# USB2Serial_FT232RL_v1_0.net
KiCad netlist of a schematic drawn in EAGLE
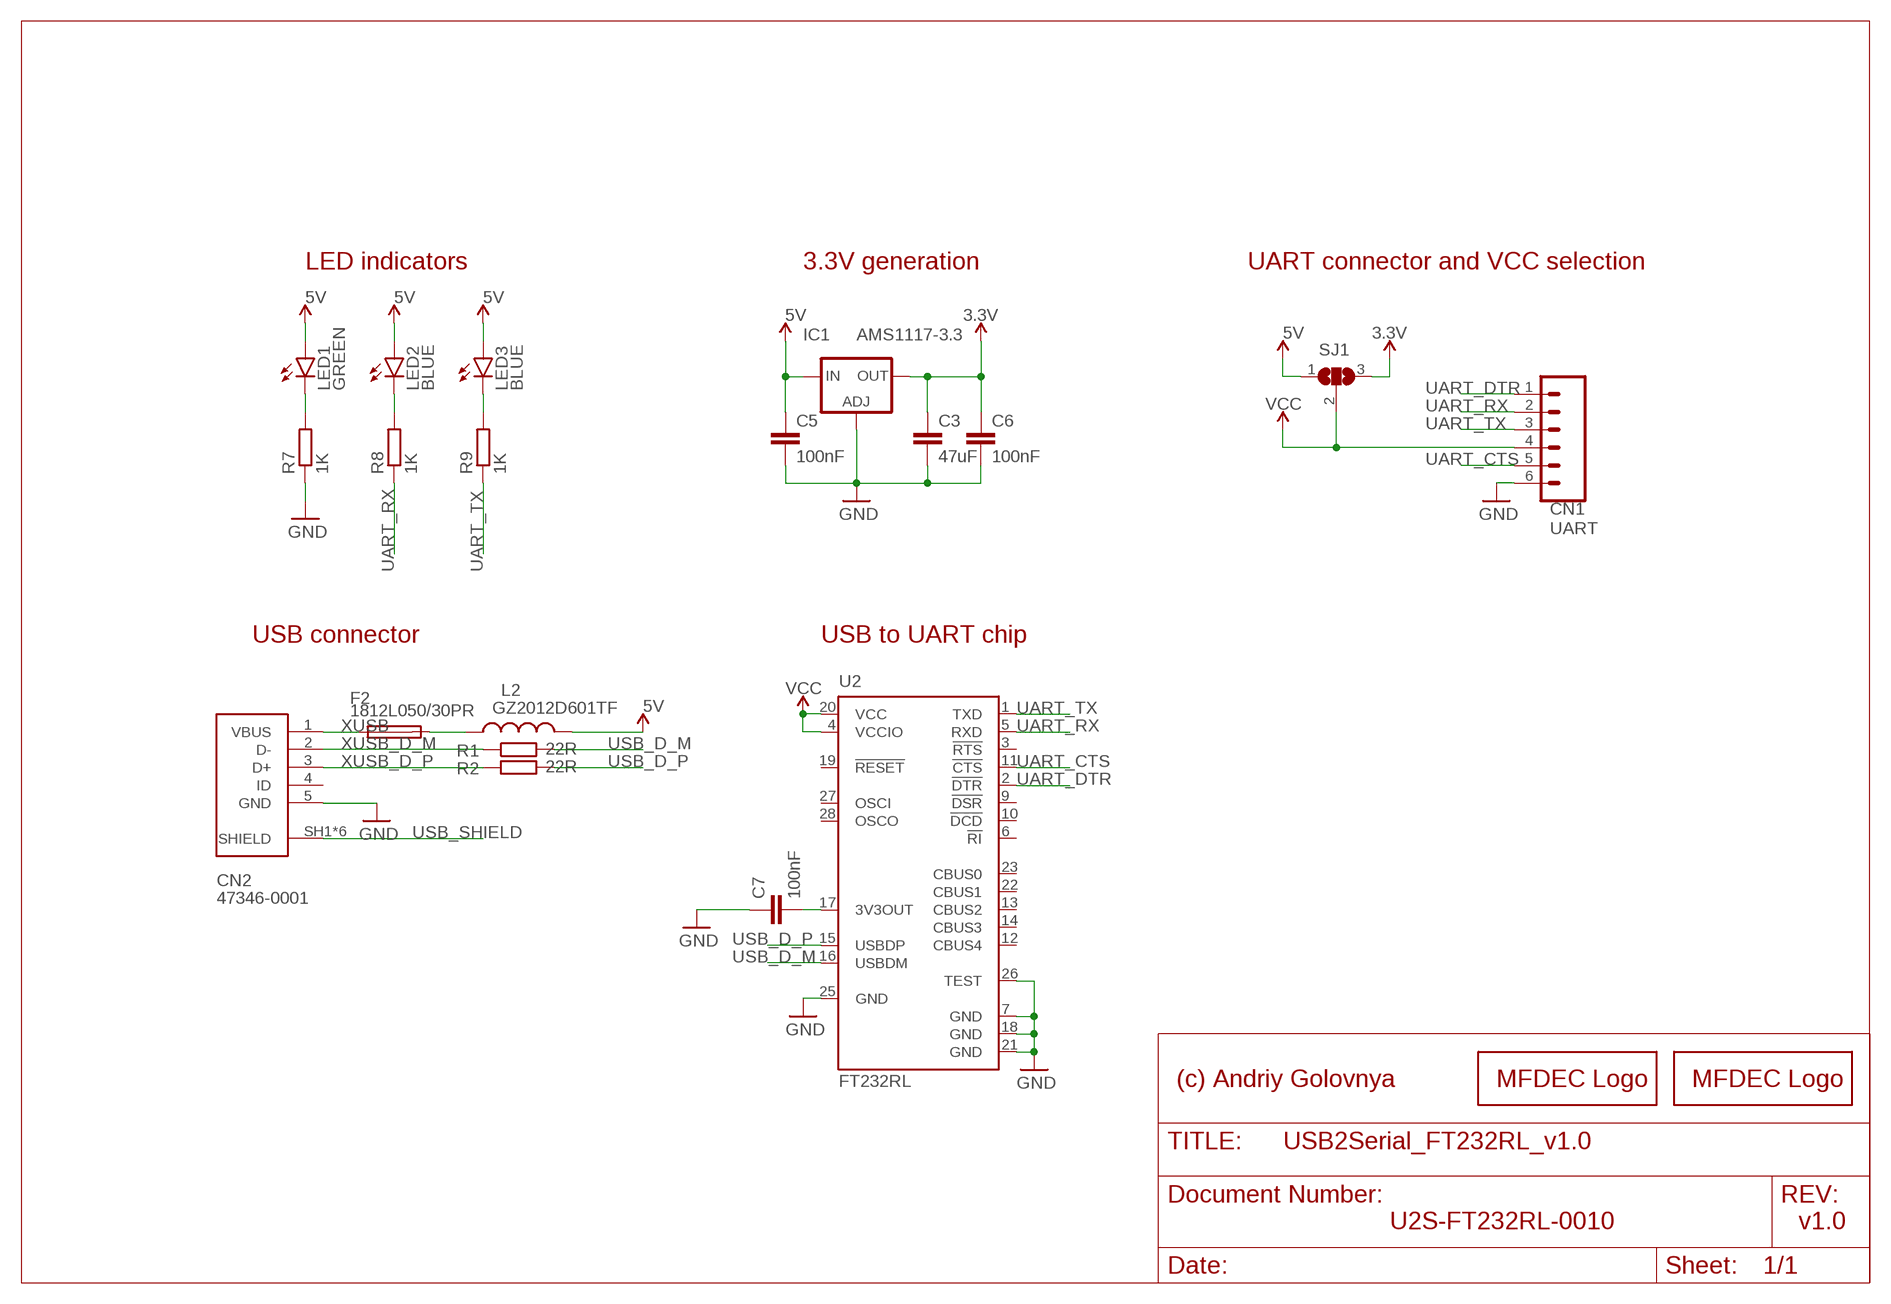
[diagram p0: schematic, sheet 1]

(export (version "E")
  (design (tool "Eeschema 10.0.6"))
  (components
    (comp (ref "C3")
      (value "47uF")
      (footprint "eagle-import:C0805")
      (libsource (lib "eagle-import") (part "C-EUC0805"))
    )
    (comp (ref "C5")
      (value "100nF")
      (footprint "eagle-import:C0402")
      (libsource (lib "eagle-import") (part "C-EUC0402"))
    )
    (comp (ref "C6")
      (value "100nF")
      (footprint "eagle-import:C0402")
      (libsource (lib "eagle-import") (part "C-EUC0402"))
    )
    (comp (ref "C7")
      (value "100nF")
      (footprint "eagle-import:C0402")
      (libsource (lib "eagle-import") (part "C-EUC0402"))
    )
    (comp (ref "CN1")
      (value "UART")
      (footprint "eagle-import:1X06_LOCK")
      (libsource (lib "eagle-import") (part "CONN_06LOCK"))
    )
    (comp (ref "CN2")
      (value "47346-0001")
      (footprint "eagle-import:MOLEX_47346-0001")
      (fields (field (name "MANUFACTURER") "Molex"))
      (libsource (lib "eagle-import") (part "47346-0001"))
    )
    (comp (ref "F2")
      (value "1812L050/30PR")
      (footprint "eagle-import:MF-SMDF050")
      (libsource (lib "eagle-import") (part "MF-SMDF050"))
    )
    (comp (ref "IC1")
      (value "AMS1117-3.3")
      (footprint "eagle-import:SOT223")
      (libsource (lib "eagle-import") (part "LD117A?S33TR"))
    )
    (comp (ref "L2")
      (value "GZ2012D601TF")
      (footprint "eagle-import:WE-CBA_0805(W=4)")
      (libsource (lib "eagle-import") (part "WE-CBA_0805_HC_782853102"))
    )
    (comp (ref "LED1")
      (value "GREEN")
      (footprint "eagle-import:SML0603")
      (libsource (lib "eagle-import") (part "LEDSML0603"))
    )
    (comp (ref "LED2")
      (value "BLUE")
      (footprint "eagle-import:SML0603")
      (libsource (lib "eagle-import") (part "LEDSML0603"))
    )
    (comp (ref "LED3")
      (value "BLUE")
      (footprint "eagle-import:SML0603")
      (libsource (lib "eagle-import") (part "LEDSML0603"))
    )
    (comp (ref "LOGO1")
      (value "MFDECLOGO_L_20MM")
      (footprint "eagle-import:MFDEC_L_20MM")
      (libsource (lib "eagle-import") (part "MFDECLOGO_L_20MM"))
    )
    (comp (ref "LOGO2")
      (value "MFDECLOGO_SQ_10MM")
      (footprint "eagle-import:MFDEC_SQ_10MM")
      (libsource (lib "eagle-import") (part "MFDECLOGO_SQ_10MM"))
    )
    (comp (ref "R1")
      (value "22R")
      (footprint "eagle-import:R0402")
      (libsource (lib "eagle-import") (part "R-EU_R0402"))
    )
    (comp (ref "R2")
      (value "22R")
      (footprint "eagle-import:R0402")
      (libsource (lib "eagle-import") (part "R-EU_R0402"))
    )
    (comp (ref "R7")
      (value "1K")
      (footprint "eagle-import:R0402")
      (libsource (lib "eagle-import") (part "R-EU_R0402"))
    )
    (comp (ref "R8")
      (value "1K")
      (footprint "eagle-import:R0402")
      (libsource (lib "eagle-import") (part "R-EU_R0402"))
    )
    (comp (ref "R9")
      (value "1K")
      (footprint "eagle-import:R0402")
      (libsource (lib "eagle-import") (part "R-EU_R0402"))
    )
    (comp (ref "SJ1")
      (value "SJ2FI")
      (footprint "eagle-import:SJ_2FI")
      (libsource (lib "eagle-import") (part "SJ2FI"))
    )
    (comp (ref "U2")
      (value "FT232RL")
      (footprint "eagle-import:SSOP28")
      (libsource (lib "eagle-import") (part "FT232RL"))
    )
  )
  (nets
    (net (code "1") (name "/UART_CTS") (class "Default")
      (node (ref "CN1") (pin "5") (pinfunction "5_5") (pintype "passive"))
      (node (ref "U2") (pin "11") (pinfunction "~{CTS}_11") (pintype "input"))
    )
    (net (code "2") (name "/UART_DTR") (class "Default")
      (node (ref "CN1") (pin "1") (pinfunction "1_1") (pintype "passive"))
      (node (ref "U2") (pin "2") (pinfunction "~{DTR}_2") (pintype "output"))
    )
    (net (code "3") (name "/UART_RX") (class "Default")
      (node (ref "CN1") (pin "2") (pinfunction "2_2") (pintype "passive"))
      (node (ref "R8") (pin "1") (pinfunction "1_1") (pintype "passive"))
      (node (ref "U2") (pin "5") (pinfunction "RXD_5") (pintype "input"))
    )
    (net (code "4") (name "/UART_TX") (class "Default")
      (node (ref "CN1") (pin "3") (pinfunction "3_3") (pintype "passive"))
      (node (ref "R9") (pin "1") (pinfunction "1_1") (pintype "passive"))
      (node (ref "U2") (pin "1") (pinfunction "TXD_1") (pintype "output"))
    )
    (net (code "5") (name "/USB_D_M") (class "Default")
      (node (ref "R1") (pin "2") (pinfunction "2_2") (pintype "passive"))
      (node (ref "U2") (pin "16") (pinfunction "USBDM_16") (pintype "bidirectional"))
    )
    (net (code "6") (name "/USB_D_P") (class "Default")
      (node (ref "R2") (pin "2") (pinfunction "2_2") (pintype "passive"))
      (node (ref "U2") (pin "15") (pinfunction "USBDP_15") (pintype "bidirectional"))
    )
    (net (code "7") (name "/USB_SHIELD") (class "Default")
      (node (ref "CN2") (pin "SH1") (pinfunction "SHIELD_SH1") (pintype "passive"))
      (node (ref "CN2") (pin "SH2") (pinfunction "SHIELD_SH2") (pintype "passive"))
      (node (ref "CN2") (pin "SH3") (pinfunction "SHIELD_SH3") (pintype "passive"))
      (node (ref "CN2") (pin "SH4") (pinfunction "SHIELD_SH4") (pintype "passive"))
      (node (ref "CN2") (pin "SH5") (pinfunction "SHIELD_SH5") (pintype "passive"))
      (node (ref "CN2") (pin "SH6") (pinfunction "SHIELD_SH6") (pintype "passive"))
    )
    (net (code "8") (name "/XUSB") (class "Default")
      (node (ref "CN2") (pin "1") (pinfunction "VBUS_1") (pintype "power_in"))
      (node (ref "F2") (pin "1") (pinfunction "1_1") (pintype "passive"))
    )
    (net (code "9") (name "/XUSB_D_M") (class "Default")
      (node (ref "CN2") (pin "2") (pinfunction "D-_2") (pintype "bidirectional"))
      (node (ref "R1") (pin "1") (pinfunction "1_1") (pintype "passive"))
    )
    (net (code "10") (name "/XUSB_D_P") (class "Default")
      (node (ref "CN2") (pin "3") (pinfunction "D+_3") (pintype "bidirectional"))
      (node (ref "R2") (pin "1") (pinfunction "1_1") (pintype "passive"))
    )
    (net (code "11") (name "3.3V") (class "Default")
      (node (ref "C3") (pin "1") (pinfunction "1_1") (pintype "passive"))
      (node (ref "C6") (pin "1") (pinfunction "1_1") (pintype "passive"))
      (node (ref "IC1") (pin "4") (pinfunction "OUT_4") (pintype "passive"))
      (node (ref "SJ1") (pin "3") (pinfunction "3_3") (pintype "passive"))
    )
    (net (code "12") (name "5V") (class "Default")
      (node (ref "C5") (pin "1") (pinfunction "1_1") (pintype "passive"))
      (node (ref "IC1") (pin "3") (pinfunction "IN_3") (pintype "input"))
      (node (ref "L2") (pin "2") (pinfunction "2_2") (pintype "passive"))
      (node (ref "LED1") (pin "A") (pinfunction "A_A") (pintype "passive"))
      (node (ref "LED2") (pin "A") (pinfunction "A_A") (pintype "passive"))
      (node (ref "LED3") (pin "A") (pinfunction "A_A") (pintype "passive"))
      (node (ref "SJ1") (pin "1") (pinfunction "1_1") (pintype "passive"))
    )
    (net (code "13") (name "GND") (class "Default")
      (node (ref "C3") (pin "2") (pinfunction "2_2") (pintype "passive"))
      (node (ref "C5") (pin "2") (pinfunction "2_2") (pintype "passive"))
      (node (ref "C6") (pin "2") (pinfunction "2_2") (pintype "passive"))
      (node (ref "C7") (pin "1") (pinfunction "1_1") (pintype "passive"))
      (node (ref "CN1") (pin "6") (pinfunction "6_6") (pintype "passive"))
      (node (ref "CN2") (pin "5") (pinfunction "GND_5") (pintype "power_in"))
      (node (ref "IC1") (pin "1") (pinfunction "ADJ_1") (pintype "input"))
      (node (ref "R7") (pin "1") (pinfunction "1_1") (pintype "passive"))
      (node (ref "U2") (pin "18") (pinfunction "GND_18") (pintype "power_in"))
      (node (ref "U2") (pin "21") (pinfunction "GND_21") (pintype "power_in"))
      (node (ref "U2") (pin "25") (pinfunction "GND_25") (pintype "power_in"))
      (node (ref "U2") (pin "26") (pinfunction "TEST_26") (pintype "input"))
      (node (ref "U2") (pin "7") (pinfunction "GND_7") (pintype "power_in"))
    )
    (net (code "14") (name "Net-(F2-Pad2)") (class "Default")
      (node (ref "F2") (pin "2") (pinfunction "2_2") (pintype "passive"))
      (node (ref "L2") (pin "1") (pinfunction "1_1") (pintype "passive"))
    )
    (net (code "15") (name "Net-(LED1-PadC)") (class "Default")
      (node (ref "LED1") (pin "C") (pinfunction "C_C") (pintype "passive"))
      (node (ref "R7") (pin "2") (pinfunction "2_2") (pintype "passive"))
    )
    (net (code "16") (name "Net-(LED2-PadC)") (class "Default")
      (node (ref "LED2") (pin "C") (pinfunction "C_C") (pintype "passive"))
      (node (ref "R8") (pin "2") (pinfunction "2_2") (pintype "passive"))
    )
    (net (code "17") (name "Net-(LED3-PadC)") (class "Default")
      (node (ref "LED3") (pin "C") (pinfunction "C_C") (pintype "passive"))
      (node (ref "R9") (pin "2") (pinfunction "2_2") (pintype "passive"))
    )
    (net (code "18") (name "Net-(U2-3V3OUT)") (class "Default")
      (node (ref "C7") (pin "2") (pinfunction "2_2") (pintype "passive"))
      (node (ref "U2") (pin "17") (pinfunction "3V3OUT_17") (pintype "output"))
    )
    (net (code "19") (name "VCC") (class "Default")
      (node (ref "CN1") (pin "4") (pinfunction "4_4") (pintype "passive"))
      (node (ref "SJ1") (pin "2") (pinfunction "2_2") (pintype "passive"))
      (node (ref "U2") (pin "20") (pinfunction "VCC_20") (pintype "power_in"))
      (node (ref "U2") (pin "4") (pinfunction "VCCIO_4") (pintype "power_in"))
    )
    (net (code "20") (name "unconnected-(CN2-ID-Pad4)") (class "Default")
      (node (ref "CN2") (pin "4") (pinfunction "ID_4") (pintype "passive"))
    )
    (net (code "21") (name "unconnected-(U2-CBUS0-Pad23)") (class "Default")
      (node (ref "U2") (pin "23") (pinfunction "CBUS0_23") (pintype "bidirectional"))
    )
    (net (code "22") (name "unconnected-(U2-CBUS1-Pad22)") (class "Default")
      (node (ref "U2") (pin "22") (pinfunction "CBUS1_22") (pintype "bidirectional"))
    )
    (net (code "23") (name "unconnected-(U2-CBUS2-Pad13)") (class "Default")
      (node (ref "U2") (pin "13") (pinfunction "CBUS2_13") (pintype "bidirectional"))
    )
    (net (code "24") (name "unconnected-(U2-CBUS3-Pad14)") (class "Default")
      (node (ref "U2") (pin "14") (pinfunction "CBUS3_14") (pintype "bidirectional"))
    )
    (net (code "25") (name "unconnected-(U2-CBUS4-Pad12)") (class "Default")
      (node (ref "U2") (pin "12") (pinfunction "CBUS4_12") (pintype "bidirectional"))
    )
    (net (code "26") (name "unconnected-(U2-OSCI-Pad27)") (class "Default")
      (node (ref "U2") (pin "27") (pinfunction "OSCI_27") (pintype "input"))
    )
    (net (code "27") (name "unconnected-(U2-OSCO-Pad28)") (class "Default")
      (node (ref "U2") (pin "28") (pinfunction "OSCO_28") (pintype "output"))
    )
    (net (code "28") (name "unconnected-(U2-~{DCD}-Pad10)") (class "Default")
      (node (ref "U2") (pin "10") (pinfunction "~{DCD}_10") (pintype "input"))
    )
    (net (code "29") (name "unconnected-(U2-~{DSR}-Pad9)") (class "Default")
      (node (ref "U2") (pin "9") (pinfunction "~{DSR}_9") (pintype "input"))
    )
    (net (code "30") (name "unconnected-(U2-~{RESET}-Pad19)") (class "Default")
      (node (ref "U2") (pin "19") (pinfunction "~{RESET}_19") (pintype "input"))
    )
    (net (code "31") (name "unconnected-(U2-~{RI}-Pad6)") (class "Default")
      (node (ref "U2") (pin "6") (pinfunction "~{RI}_6") (pintype "input"))
    )
    (net (code "32") (name "unconnected-(U2-~{RTS}-Pad3)") (class "Default")
      (node (ref "U2") (pin "3") (pinfunction "~{RTS}_3") (pintype "output"))
    )
  )
)
